# Headlightsv2.net
KiCad netlist of a schematic drawn in EAGLE
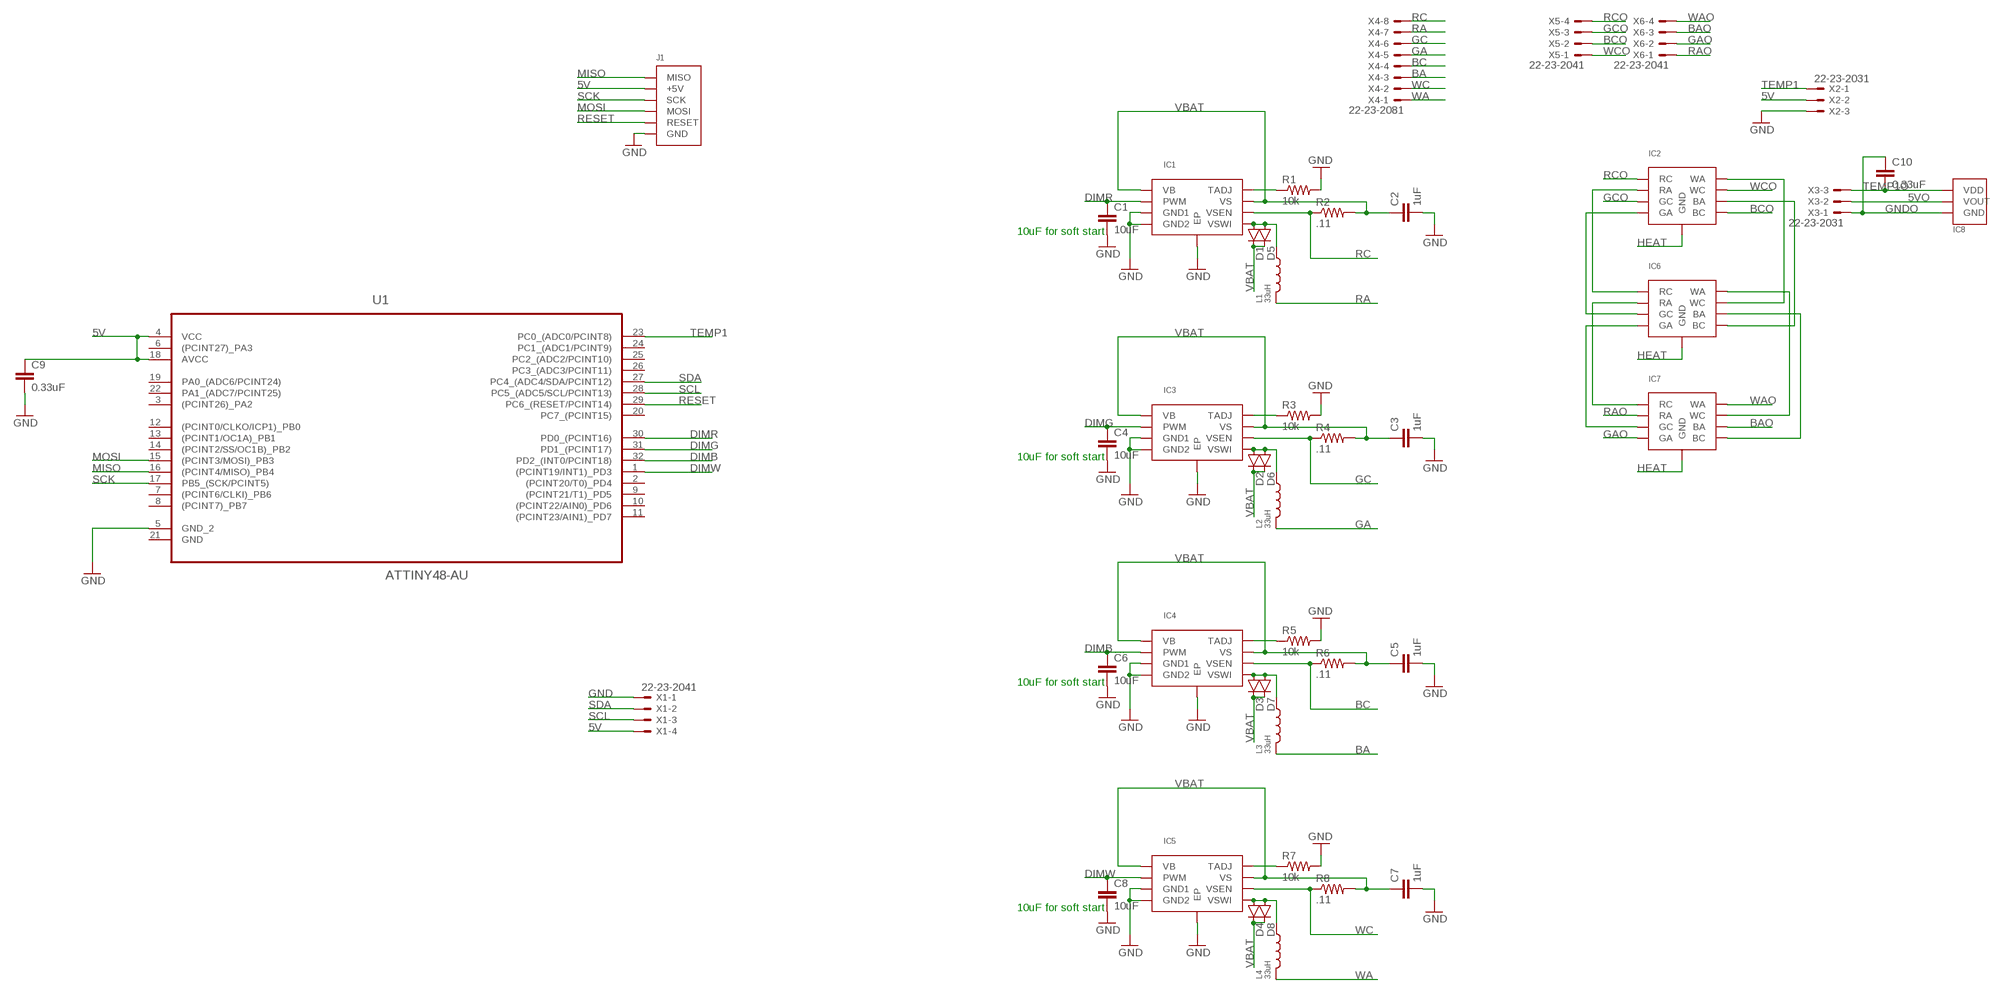
[diagram p0: schematic, sheet 1]

(export (version "E")
  (design (tool "Eeschema 10.0.6"))
  (components
    (comp (ref "C1")
      (value "10uF")
      (footprint "eagle-import:0805-CAP")
      (libsource (lib "eagle-import") (part "10UF10V10%(0805)"))
    )
    (comp (ref "C2")
      (value "1uF")
      (footprint "eagle-import:1206-CAP")
      (libsource (lib "eagle-import") (part "2.2UF50V10%(1206)"))
    )
    (comp (ref "C3")
      (value "1uF")
      (footprint "eagle-import:1206-CAP")
      (libsource (lib "eagle-import") (part "2.2UF50V10%(1206)"))
    )
    (comp (ref "C4")
      (value "10uF")
      (footprint "eagle-import:0805-CAP")
      (libsource (lib "eagle-import") (part "10UF10V10%(0805)"))
    )
    (comp (ref "C5")
      (value "1uF")
      (footprint "eagle-import:1206-CAP")
      (libsource (lib "eagle-import") (part "2.2UF50V10%(1206)"))
    )
    (comp (ref "C6")
      (value "10uF")
      (footprint "eagle-import:0805-CAP")
      (libsource (lib "eagle-import") (part "10UF10V10%(0805)"))
    )
    (comp (ref "C7")
      (value "1uF")
      (footprint "eagle-import:1206-CAP")
      (libsource (lib "eagle-import") (part "2.2UF50V10%(1206)"))
    )
    (comp (ref "C8")
      (value "10uF")
      (footprint "eagle-import:0805-CAP")
      (libsource (lib "eagle-import") (part "10UF10V10%(0805)"))
    )
    (comp (ref "C9")
      (value "0.33uF")
      (footprint "eagle-import:0805-CAP")
      (libsource (lib "eagle-import") (part "0.33UF-50V-10%(0805)"))
    )
    (comp (ref "C10")
      (value "0.33uF")
      (footprint "eagle-import:0805-CAP")
      (libsource (lib "eagle-import") (part "0.33UF-50V-10%(0805)"))
    )
    (comp (ref "D1")
      (value "DIODESMA-ALT")
      (footprint "eagle-import:SMA-DIODE_ALT")
      (libsource (lib "eagle-import") (part "DIODESMA-ALT"))
    )
    (comp (ref "D2")
      (value "DIODESMA-ALT")
      (footprint "eagle-import:SMA-DIODE_ALT")
      (libsource (lib "eagle-import") (part "DIODESMA-ALT"))
    )
    (comp (ref "D3")
      (value "DIODESMA-ALT")
      (footprint "eagle-import:SMA-DIODE_ALT")
      (libsource (lib "eagle-import") (part "DIODESMA-ALT"))
    )
    (comp (ref "D4")
      (value "DIODESMA-ALT")
      (footprint "eagle-import:SMA-DIODE_ALT")
      (libsource (lib "eagle-import") (part "DIODESMA-ALT"))
    )
    (comp (ref "D5")
      (value "DIODESMA-ALT")
      (footprint "eagle-import:SMA-DIODE_ALT")
      (libsource (lib "eagle-import") (part "DIODESMA-ALT"))
    )
    (comp (ref "D6")
      (value "DIODESMA-ALT")
      (footprint "eagle-import:SMA-DIODE_ALT")
      (libsource (lib "eagle-import") (part "DIODESMA-ALT"))
    )
    (comp (ref "D7")
      (value "DIODESMA-ALT")
      (footprint "eagle-import:SMA-DIODE_ALT")
      (libsource (lib "eagle-import") (part "DIODESMA-ALT"))
    )
    (comp (ref "D8")
      (value "DIODESMA-ALT")
      (footprint "eagle-import:SMA-DIODE_ALT")
      (libsource (lib "eagle-import") (part "DIODESMA-ALT"))
    )
    (comp (ref "IC1")
      (value "ILD6150_LED_DRIVER")
      (footprint "eagle-import:PG-DSO-8-27")
      (libsource (lib "eagle-import") (part "ILD6150_LED_DRIVER"))
    )
    (comp (ref "IC2")
      (value "LED_RGBW_CONF2")
      (footprint "eagle-import:LED_RGBW_CUSTOM")
      (libsource (lib "eagle-import") (part "LED_RGBW_CONF2"))
    )
    (comp (ref "IC3")
      (value "ILD6150_LED_DRIVER")
      (footprint "eagle-import:PG-DSO-8-27")
      (libsource (lib "eagle-import") (part "ILD6150_LED_DRIVER"))
    )
    (comp (ref "IC4")
      (value "ILD6150_LED_DRIVER")
      (footprint "eagle-import:PG-DSO-8-27")
      (libsource (lib "eagle-import") (part "ILD6150_LED_DRIVER"))
    )
    (comp (ref "IC5")
      (value "ILD6150_LED_DRIVER")
      (footprint "eagle-import:PG-DSO-8-27")
      (libsource (lib "eagle-import") (part "ILD6150_LED_DRIVER"))
    )
    (comp (ref "IC6")
      (value "LED_RGBW_CONF2")
      (footprint "eagle-import:LED_RGBW_CUSTOM")
      (libsource (lib "eagle-import") (part "LED_RGBW_CONF2"))
    )
    (comp (ref "IC7")
      (value "LED_RGBW_CONF2")
      (footprint "eagle-import:LED_RGBW_CUSTOM")
      (libsource (lib "eagle-import") (part "LED_RGBW_CONF2"))
    )
    (comp (ref "IC8")
      (value "TEMP_MCP9701")
      (footprint "eagle-import:SOT-23-3")
      (libsource (lib "eagle-import") (part "TEMP_MCP9701"))
    )
    (comp (ref "J1")
      (value "ISPHEADER")
      (footprint "eagle-import:2X3PIN_.1'")
      (libsource (lib "eagle-import") (part "ISPHEADER"))
    )
    (comp (ref "L1")
      (value "33uH")
      (footprint "eagle-import:IND_RLB_SERIES")
      (libsource (lib "eagle-import") (part "CHIP_IND4"))
    )
    (comp (ref "L2")
      (value "33uH")
      (footprint "eagle-import:IND_RLB_SERIES")
      (libsource (lib "eagle-import") (part "CHIP_IND4"))
    )
    (comp (ref "L3")
      (value "33uH")
      (footprint "eagle-import:IND_RLB_SERIES")
      (libsource (lib "eagle-import") (part "CHIP_IND4"))
    )
    (comp (ref "L4")
      (value "33uH")
      (footprint "eagle-import:IND_RLB_SERIES")
      (libsource (lib "eagle-import") (part "CHIP_IND4"))
    )
    (comp (ref "R1")
      (value "10k")
      (footprint "eagle-import:0805")
      (libsource (lib "eagle-import") (part "0.3OHM-1/8W-1%(0805)"))
    )
    (comp (ref "R2")
      (value ".11")
      (footprint "eagle-import:R2010")
      (libsource (lib "eagle-import") (part "0.11OHM1/2W1%(2010)"))
    )
    (comp (ref "R3")
      (value "10k")
      (footprint "eagle-import:0805")
      (libsource (lib "eagle-import") (part "0.3OHM-1/8W-1%(0805)"))
    )
    (comp (ref "R4")
      (value ".11")
      (footprint "eagle-import:R2010")
      (libsource (lib "eagle-import") (part "0.11OHM1/2W1%(2010)"))
    )
    (comp (ref "R5")
      (value "10k")
      (footprint "eagle-import:0805")
      (libsource (lib "eagle-import") (part "0.3OHM-1/8W-1%(0805)"))
    )
    (comp (ref "R6")
      (value ".11")
      (footprint "eagle-import:R2010")
      (libsource (lib "eagle-import") (part "0.11OHM1/2W1%(2010)"))
    )
    (comp (ref "R7")
      (value "10k")
      (footprint "eagle-import:0805")
      (libsource (lib "eagle-import") (part "0.3OHM-1/8W-1%(0805)"))
    )
    (comp (ref "R8")
      (value ".11")
      (footprint "eagle-import:R2010")
      (libsource (lib "eagle-import") (part "0.11OHM1/2W1%(2010)"))
    )
    (comp (ref "U1")
      (value "ATTINY48-AU")
      (footprint "eagle-import:QFP80P900X900X120-32N")
      (libsource (lib "eagle-import") (part "ATTINY48-AU"))
    )
    (comp (ref "X1")
      (value "22-23-2041")
      (footprint "eagle-import:22-23-2041")
      (fields (field (name "MF") "MOLEX"))
      (libsource (lib "eagle-import") (part "22-23-2041"))
    )
    (comp (ref "X2")
      (value "22-23-2031")
      (footprint "eagle-import:22-23-2031")
      (fields (field (name "MF") "MOLEX"))
      (libsource (lib "eagle-import") (part "22-23-2031"))
    )
    (comp (ref "X3")
      (value "22-23-2031")
      (footprint "eagle-import:22-23-2031")
      (fields (field (name "MF") "MOLEX"))
      (libsource (lib "eagle-import") (part "22-23-2031"))
    )
    (comp (ref "X4")
      (value "22-23-2081")
      (footprint "eagle-import:22-23-2081")
      (fields (field (name "MF") "MOLEX"))
      (libsource (lib "eagle-import") (part "22-23-2081"))
    )
    (comp (ref "X5")
      (value "22-23-2041")
      (footprint "eagle-import:22-23-2041")
      (fields (field (name "MF") "MOLEX"))
      (libsource (lib "eagle-import") (part "22-23-2041"))
    )
    (comp (ref "X6")
      (value "22-23-2041")
      (footprint "eagle-import:22-23-2041")
      (fields (field (name "MF") "MOLEX"))
      (libsource (lib "eagle-import") (part "22-23-2041"))
    )
  )
  (nets
    (net (code "1") (name "/5V") (class "Default")
      (node (ref "C9") (pin "1") (pinfunction "1_1") (pintype "passive"))
      (node (ref "J1") (pin "P$2") (pinfunction "+5V_P$2") (pintype "bidirectional"))
      (node (ref "U1") (pin "18") (pinfunction "AVCC_18") (pintype "power_in"))
      (node (ref "U1") (pin "4") (pinfunction "VCC_4") (pintype "power_in"))
      (node (ref "X1") (pin "4") (pinfunction "S_4") (pintype "passive"))
      (node (ref "X2") (pin "2") (pinfunction "S_2") (pintype "passive"))
    )
    (net (code "2") (name "/5VO") (class "Default")
      (node (ref "IC8") (pin "2") (pinfunction "VOUT_2") (pintype "bidirectional"))
      (node (ref "X3") (pin "2") (pinfunction "S_2") (pintype "passive"))
    )
    (net (code "3") (name "/BA") (class "Default")
      (node (ref "L3") (pin "P$1") (pinfunction "P$1_P$1") (pintype "bidirectional"))
      (node (ref "X4") (pin "3") (pinfunction "S_3") (pintype "passive"))
    )
    (net (code "4") (name "/BAO") (class "Default")
      (node (ref "IC7") (pin "6") (pinfunction "BA_6") (pintype "bidirectional"))
      (node (ref "X6") (pin "3") (pinfunction "S_3") (pintype "passive"))
    )
    (net (code "5") (name "/BC") (class "Default")
      (node (ref "IC4") (pin "P$6") (pinfunction "VSEN_P$6") (pintype "bidirectional"))
      (node (ref "R6") (pin "1") (pinfunction "1_1") (pintype "passive"))
      (node (ref "X4") (pin "4") (pinfunction "S_4") (pintype "passive"))
    )
    (net (code "6") (name "/BCO") (class "Default")
      (node (ref "IC2") (pin "5") (pinfunction "BC_5") (pintype "bidirectional"))
      (node (ref "X5") (pin "2") (pinfunction "S_2") (pintype "passive"))
    )
    (net (code "7") (name "/DIMB") (class "Default")
      (node (ref "C6") (pin "1") (pinfunction "1_1") (pintype "passive"))
      (node (ref "IC4") (pin "P$2") (pinfunction "PWM_P$2") (pintype "bidirectional"))
      (node (ref "U1") (pin "32") (pinfunction "PD2_(INT0/PCINT18)_32") (pintype "bidirectional"))
    )
    (net (code "8") (name "/DIMG") (class "Default")
      (node (ref "C4") (pin "1") (pinfunction "1_1") (pintype "passive"))
      (node (ref "IC3") (pin "P$2") (pinfunction "PWM_P$2") (pintype "bidirectional"))
      (node (ref "U1") (pin "31") (pinfunction "PD1_(PCINT17)_31") (pintype "bidirectional"))
    )
    (net (code "9") (name "/DIMR") (class "Default")
      (node (ref "C1") (pin "1") (pinfunction "1_1") (pintype "passive"))
      (node (ref "IC1") (pin "P$2") (pinfunction "PWM_P$2") (pintype "bidirectional"))
      (node (ref "U1") (pin "30") (pinfunction "PD0_(PCINT16)_30") (pintype "bidirectional"))
    )
    (net (code "10") (name "/DIMW") (class "Default")
      (node (ref "C8") (pin "1") (pinfunction "1_1") (pintype "passive"))
      (node (ref "IC5") (pin "P$2") (pinfunction "PWM_P$2") (pintype "bidirectional"))
      (node (ref "U1") (pin "1") (pinfunction "(PCINT19/INT1)_PD3_1") (pintype "bidirectional"))
    )
    (net (code "11") (name "/GA") (class "Default")
      (node (ref "L2") (pin "P$1") (pinfunction "P$1_P$1") (pintype "bidirectional"))
      (node (ref "X4") (pin "5") (pinfunction "S_5") (pintype "passive"))
    )
    (net (code "12") (name "/GAO") (class "Default")
      (node (ref "IC7") (pin "4") (pinfunction "GA_4") (pintype "bidirectional"))
      (node (ref "X6") (pin "2") (pinfunction "S_2") (pintype "passive"))
    )
    (net (code "13") (name "/GC") (class "Default")
      (node (ref "IC3") (pin "P$6") (pinfunction "VSEN_P$6") (pintype "bidirectional"))
      (node (ref "R4") (pin "1") (pinfunction "1_1") (pintype "passive"))
      (node (ref "X4") (pin "6") (pinfunction "S_6") (pintype "passive"))
    )
    (net (code "14") (name "/GCO") (class "Default")
      (node (ref "IC2") (pin "3") (pinfunction "GC_3") (pintype "bidirectional"))
      (node (ref "X5") (pin "3") (pinfunction "S_3") (pintype "passive"))
    )
    (net (code "15") (name "/GNDO") (class "Default")
      (node (ref "C10") (pin "1") (pinfunction "1_1") (pintype "passive"))
      (node (ref "IC8") (pin "3") (pinfunction "GND_3") (pintype "bidirectional"))
      (node (ref "X3") (pin "1") (pinfunction "S_1") (pintype "passive"))
    )
    (net (code "16") (name "/HEAT") (class "Default")
      (node (ref "IC2") (pin "9") (pinfunction "GND_9") (pintype "bidirectional"))
      (node (ref "IC6") (pin "9") (pinfunction "GND_9") (pintype "bidirectional"))
      (node (ref "IC7") (pin "9") (pinfunction "GND_9") (pintype "bidirectional"))
    )
    (net (code "17") (name "/MISO") (class "Default")
      (node (ref "J1") (pin "P$1") (pinfunction "MISO_P$1") (pintype "bidirectional"))
      (node (ref "U1") (pin "16") (pinfunction "(PCINT4/MISO)_PB4_16") (pintype "bidirectional"))
    )
    (net (code "18") (name "/MOSI") (class "Default")
      (node (ref "J1") (pin "P$4") (pinfunction "MOSI_P$4") (pintype "bidirectional"))
      (node (ref "U1") (pin "15") (pinfunction "(PCINT3/MOSI)_PB3_15") (pintype "bidirectional"))
    )
    (net (code "19") (name "/RA") (class "Default")
      (node (ref "L1") (pin "P$1") (pinfunction "P$1_P$1") (pintype "bidirectional"))
      (node (ref "X4") (pin "7") (pinfunction "S_7") (pintype "passive"))
    )
    (net (code "20") (name "/RAO") (class "Default")
      (node (ref "IC7") (pin "2") (pinfunction "RA_2") (pintype "bidirectional"))
      (node (ref "X6") (pin "1") (pinfunction "S_1") (pintype "passive"))
    )
    (net (code "21") (name "/RC") (class "Default")
      (node (ref "IC1") (pin "P$6") (pinfunction "VSEN_P$6") (pintype "bidirectional"))
      (node (ref "R2") (pin "1") (pinfunction "1_1") (pintype "passive"))
      (node (ref "X4") (pin "8") (pinfunction "S_8") (pintype "passive"))
    )
    (net (code "22") (name "/RCO") (class "Default")
      (node (ref "IC2") (pin "1") (pinfunction "RC_1") (pintype "bidirectional"))
      (node (ref "X5") (pin "4") (pinfunction "S_4") (pintype "passive"))
    )
    (net (code "23") (name "/RESET") (class "Default")
      (node (ref "J1") (pin "P$5") (pinfunction "RESET_P$5") (pintype "bidirectional"))
      (node (ref "U1") (pin "29") (pinfunction "PC6_(RESET/PCINT14)_29") (pintype "bidirectional"))
    )
    (net (code "24") (name "/SCK") (class "Default")
      (node (ref "J1") (pin "P$3") (pinfunction "SCK_P$3") (pintype "bidirectional"))
      (node (ref "U1") (pin "17") (pinfunction "PB5_(SCK/PCINT5)_17") (pintype "bidirectional"))
    )
    (net (code "25") (name "/SCL") (class "Default")
      (node (ref "U1") (pin "28") (pinfunction "PC5_(ADC5/SCL/PCINT13)_28") (pintype "bidirectional"))
      (node (ref "X1") (pin "3") (pinfunction "S_3") (pintype "passive"))
    )
    (net (code "26") (name "/SDA") (class "Default")
      (node (ref "U1") (pin "27") (pinfunction "PC4_(ADC4/SDA/PCINT12)_27") (pintype "bidirectional"))
      (node (ref "X1") (pin "2") (pinfunction "S_2") (pintype "passive"))
    )
    (net (code "27") (name "/TEMP1") (class "Default")
      (node (ref "U1") (pin "23") (pinfunction "PC0_(ADC0/PCINT8)_23") (pintype "bidirectional"))
      (node (ref "X2") (pin "1") (pinfunction "S_1") (pintype "passive"))
    )
    (net (code "28") (name "/TEMP1O") (class "Default")
      (node (ref "C10") (pin "2") (pinfunction "2_2") (pintype "passive"))
      (node (ref "IC8") (pin "1") (pinfunction "VDD_1") (pintype "bidirectional"))
      (node (ref "X3") (pin "3") (pinfunction "S_3") (pintype "passive"))
    )
    (net (code "29") (name "/VBAT") (class "Default")
      (node (ref "C2") (pin "1") (pinfunction "1_1") (pintype "passive"))
      (node (ref "C3") (pin "1") (pinfunction "1_1") (pintype "passive"))
      (node (ref "C5") (pin "1") (pinfunction "1_1") (pintype "passive"))
      (node (ref "C7") (pin "1") (pinfunction "1_1") (pintype "passive"))
      (node (ref "D1") (pin "C") (pinfunction "C_C") (pintype "passive"))
      (node (ref "D2") (pin "C") (pinfunction "C_C") (pintype "passive"))
      (node (ref "D3") (pin "C") (pinfunction "C_C") (pintype "passive"))
      (node (ref "D4") (pin "C") (pinfunction "C_C") (pintype "passive"))
      (node (ref "D5") (pin "C") (pinfunction "C_C") (pintype "passive"))
      (node (ref "D6") (pin "C") (pinfunction "C_C") (pintype "passive"))
      (node (ref "D7") (pin "C") (pinfunction "C_C") (pintype "passive"))
      (node (ref "D8") (pin "C") (pinfunction "C_C") (pintype "passive"))
      (node (ref "IC1") (pin "P$1") (pinfunction "VB_P$1") (pintype "bidirectional"))
      (node (ref "IC1") (pin "P$7") (pinfunction "VS_P$7") (pintype "bidirectional"))
      (node (ref "IC3") (pin "P$1") (pinfunction "VB_P$1") (pintype "bidirectional"))
      (node (ref "IC3") (pin "P$7") (pinfunction "VS_P$7") (pintype "bidirectional"))
      (node (ref "IC4") (pin "P$1") (pinfunction "VB_P$1") (pintype "bidirectional"))
      (node (ref "IC4") (pin "P$7") (pinfunction "VS_P$7") (pintype "bidirectional"))
      (node (ref "IC5") (pin "P$1") (pinfunction "VB_P$1") (pintype "bidirectional"))
      (node (ref "IC5") (pin "P$7") (pinfunction "VS_P$7") (pintype "bidirectional"))
      (node (ref "R2") (pin "2") (pinfunction "2_2") (pintype "passive"))
      (node (ref "R4") (pin "2") (pinfunction "2_2") (pintype "passive"))
      (node (ref "R6") (pin "2") (pinfunction "2_2") (pintype "passive"))
      (node (ref "R8") (pin "2") (pinfunction "2_2") (pintype "passive"))
    )
    (net (code "30") (name "/WA") (class "Default")
      (node (ref "L4") (pin "P$1") (pinfunction "P$1_P$1") (pintype "bidirectional"))
      (node (ref "X4") (pin "1") (pinfunction "S_1") (pintype "passive"))
    )
    (net (code "31") (name "/WAO") (class "Default")
      (node (ref "IC7") (pin "8") (pinfunction "WA_8") (pintype "bidirectional"))
      (node (ref "X6") (pin "4") (pinfunction "S_4") (pintype "passive"))
    )
    (net (code "32") (name "/WC") (class "Default")
      (node (ref "IC5") (pin "P$6") (pinfunction "VSEN_P$6") (pintype "bidirectional"))
      (node (ref "R8") (pin "1") (pinfunction "1_1") (pintype "passive"))
      (node (ref "X4") (pin "2") (pinfunction "S_2") (pintype "passive"))
    )
    (net (code "33") (name "/WCO") (class "Default")
      (node (ref "IC2") (pin "7") (pinfunction "WC_7") (pintype "bidirectional"))
      (node (ref "X5") (pin "1") (pinfunction "S_1") (pintype "passive"))
    )
    (net (code "34") (name "GND") (class "Default")
      (node (ref "C1") (pin "2") (pinfunction "2_2") (pintype "passive"))
      (node (ref "C2") (pin "2") (pinfunction "2_2") (pintype "passive"))
      (node (ref "C3") (pin "2") (pinfunction "2_2") (pintype "passive"))
      (node (ref "C4") (pin "2") (pinfunction "2_2") (pintype "passive"))
      (node (ref "C5") (pin "2") (pinfunction "2_2") (pintype "passive"))
      (node (ref "C6") (pin "2") (pinfunction "2_2") (pintype "passive"))
      (node (ref "C7") (pin "2") (pinfunction "2_2") (pintype "passive"))
      (node (ref "C8") (pin "2") (pinfunction "2_2") (pintype "passive"))
      (node (ref "C9") (pin "2") (pinfunction "2_2") (pintype "passive"))
      (node (ref "IC1") (pin "P$3") (pinfunction "GND1_P$3") (pintype "bidirectional"))
      (node (ref "IC1") (pin "P$4") (pinfunction "GND2_P$4") (pintype "bidirectional"))
      (node (ref "IC1") (pin "P$9") (pinfunction "EP_P$9") (pintype "bidirectional"))
      (node (ref "IC3") (pin "P$3") (pinfunction "GND1_P$3") (pintype "bidirectional"))
      (node (ref "IC3") (pin "P$4") (pinfunction "GND2_P$4") (pintype "bidirectional"))
      (node (ref "IC3") (pin "P$9") (pinfunction "EP_P$9") (pintype "bidirectional"))
      (node (ref "IC4") (pin "P$3") (pinfunction "GND1_P$3") (pintype "bidirectional"))
      (node (ref "IC4") (pin "P$4") (pinfunction "GND2_P$4") (pintype "bidirectional"))
      (node (ref "IC4") (pin "P$9") (pinfunction "EP_P$9") (pintype "bidirectional"))
      (node (ref "IC5") (pin "P$3") (pinfunction "GND1_P$3") (pintype "bidirectional"))
      (node (ref "IC5") (pin "P$4") (pinfunction "GND2_P$4") (pintype "bidirectional"))
      (node (ref "IC5") (pin "P$9") (pinfunction "EP_P$9") (pintype "bidirectional"))
      (node (ref "J1") (pin "P$6") (pinfunction "GND_P$6") (pintype "bidirectional"))
      (node (ref "R1") (pin "2") (pinfunction "2_2") (pintype "passive"))
      (node (ref "R3") (pin "2") (pinfunction "2_2") (pintype "passive"))
      (node (ref "R5") (pin "2") (pinfunction "2_2") (pintype "passive"))
      (node (ref "R7") (pin "2") (pinfunction "2_2") (pintype "passive"))
      (node (ref "U1") (pin "5") (pinfunction "GND_2_5") (pintype "passive"))
      (node (ref "X1") (pin "1") (pinfunction "S_1") (pintype "passive"))
      (node (ref "X2") (pin "3") (pinfunction "S_3") (pintype "passive"))
    )
    (net (code "35") (name "Net-(IC1-TADJ)") (class "Default")
      (node (ref "IC1") (pin "P$8") (pinfunction "TADJ_P$8") (pintype "bidirectional"))
      (node (ref "R1") (pin "1") (pinfunction "1_1") (pintype "passive"))
    )
    (net (code "36") (name "Net-(IC1-VSWI)") (class "Default")
      (node (ref "D1") (pin "A") (pinfunction "A_A") (pintype "passive"))
      (node (ref "D5") (pin "A") (pinfunction "A_A") (pintype "passive"))
      (node (ref "IC1") (pin "P$5") (pinfunction "VSWI_P$5") (pintype "bidirectional"))
      (node (ref "L1") (pin "P$2") (pinfunction "P$2_P$2") (pintype "bidirectional"))
    )
    (net (code "37") (name "Net-(IC2-BA)") (class "Default")
      (node (ref "IC2") (pin "6") (pinfunction "BA_6") (pintype "bidirectional"))
      (node (ref "IC6") (pin "5") (pinfunction "BC_5") (pintype "bidirectional"))
    )
    (net (code "38") (name "Net-(IC2-GA)") (class "Default")
      (node (ref "IC2") (pin "4") (pinfunction "GA_4") (pintype "bidirectional"))
      (node (ref "IC6") (pin "3") (pinfunction "GC_3") (pintype "bidirectional"))
    )
    (net (code "39") (name "Net-(IC2-RA)") (class "Default")
      (node (ref "IC2") (pin "2") (pinfunction "RA_2") (pintype "bidirectional"))
      (node (ref "IC6") (pin "1") (pinfunction "RC_1") (pintype "bidirectional"))
    )
    (net (code "40") (name "Net-(IC2-WA)") (class "Default")
      (node (ref "IC2") (pin "8") (pinfunction "WA_8") (pintype "bidirectional"))
      (node (ref "IC6") (pin "7") (pinfunction "WC_7") (pintype "bidirectional"))
    )
    (net (code "41") (name "Net-(IC3-TADJ)") (class "Default")
      (node (ref "IC3") (pin "P$8") (pinfunction "TADJ_P$8") (pintype "bidirectional"))
      (node (ref "R3") (pin "1") (pinfunction "1_1") (pintype "passive"))
    )
    (net (code "42") (name "Net-(IC3-VSWI)") (class "Default")
      (node (ref "D2") (pin "A") (pinfunction "A_A") (pintype "passive"))
      (node (ref "D6") (pin "A") (pinfunction "A_A") (pintype "passive"))
      (node (ref "IC3") (pin "P$5") (pinfunction "VSWI_P$5") (pintype "bidirectional"))
      (node (ref "L2") (pin "P$2") (pinfunction "P$2_P$2") (pintype "bidirectional"))
    )
    (net (code "43") (name "Net-(IC4-TADJ)") (class "Default")
      (node (ref "IC4") (pin "P$8") (pinfunction "TADJ_P$8") (pintype "bidirectional"))
      (node (ref "R5") (pin "1") (pinfunction "1_1") (pintype "passive"))
    )
    (net (code "44") (name "Net-(IC4-VSWI)") (class "Default")
      (node (ref "D3") (pin "A") (pinfunction "A_A") (pintype "passive"))
      (node (ref "D7") (pin "A") (pinfunction "A_A") (pintype "passive"))
      (node (ref "IC4") (pin "P$5") (pinfunction "VSWI_P$5") (pintype "bidirectional"))
      (node (ref "L3") (pin "P$2") (pinfunction "P$2_P$2") (pintype "bidirectional"))
    )
    (net (code "45") (name "Net-(IC5-TADJ)") (class "Default")
      (node (ref "IC5") (pin "P$8") (pinfunction "TADJ_P$8") (pintype "bidirectional"))
      (node (ref "R7") (pin "1") (pinfunction "1_1") (pintype "passive"))
    )
    (net (code "46") (name "Net-(IC5-VSWI)") (class "Default")
      (node (ref "D4") (pin "A") (pinfunction "A_A") (pintype "passive"))
      (node (ref "D8") (pin "A") (pinfunction "A_A") (pintype "passive"))
      (node (ref "IC5") (pin "P$5") (pinfunction "VSWI_P$5") (pintype "bidirectional"))
      (node (ref "L4") (pin "P$2") (pinfunction "P$2_P$2") (pintype "bidirectional"))
    )
    (net (code "47") (name "Net-(IC6-BA)") (class "Default")
      (node (ref "IC6") (pin "6") (pinfunction "BA_6") (pintype "bidirectional"))
      (node (ref "IC7") (pin "5") (pinfunction "BC_5") (pintype "bidirectional"))
    )
    (net (code "48") (name "Net-(IC6-GA)") (class "Default")
      (node (ref "IC6") (pin "4") (pinfunction "GA_4") (pintype "bidirectional"))
      (node (ref "IC7") (pin "3") (pinfunction "GC_3") (pintype "bidirectional"))
    )
    (net (code "49") (name "Net-(IC6-RA)") (class "Default")
      (node (ref "IC6") (pin "2") (pinfunction "RA_2") (pintype "bidirectional"))
      (node (ref "IC7") (pin "1") (pinfunction "RC_1") (pintype "bidirectional"))
    )
    (net (code "50") (name "Net-(IC6-WA)") (class "Default")
      (node (ref "IC6") (pin "8") (pinfunction "WA_8") (pintype "bidirectional"))
      (node (ref "IC7") (pin "7") (pinfunction "WC_7") (pintype "bidirectional"))
    )
    (net (code "51") (name "unconnected-(U1-(PCINT0{slash}CLKO{slash}ICP1)_PB0-Pad12)") (class "Default")
      (node (ref "U1") (pin "12") (pinfunction "(PCINT0/CLKO/ICP1)_PB0_12") (pintype "bidirectional"))
    )
    (net (code "52") (name "unconnected-(U1-(PCINT1{slash}OC1A)_PB1-Pad13)") (class "Default")
      (node (ref "U1") (pin "13") (pinfunction "(PCINT1/OC1A)_PB1_13") (pintype "bidirectional"))
    )
    (net (code "53") (name "unconnected-(U1-(PCINT2{slash}SS{slash}OC1B)_PB2-Pad14)") (class "Default")
      (node (ref "U1") (pin "14") (pinfunction "(PCINT2/SS/OC1B)_PB2_14") (pintype "bidirectional"))
    )
    (net (code "54") (name "unconnected-(U1-(PCINT6{slash}CLKI)_PB6-Pad7)") (class "Default")
      (node (ref "U1") (pin "7") (pinfunction "(PCINT6/CLKI)_PB6_7") (pintype "bidirectional"))
    )
    (net (code "55") (name "unconnected-(U1-(PCINT7)_PB7-Pad8)") (class "Default")
      (node (ref "U1") (pin "8") (pinfunction "(PCINT7)_PB7_8") (pintype "bidirectional"))
    )
    (net (code "56") (name "unconnected-(U1-(PCINT20{slash}T0)_PD4-Pad2)") (class "Default")
      (node (ref "U1") (pin "2") (pinfunction "(PCINT20/T0)_PD4_2") (pintype "bidirectional"))
    )
    (net (code "57") (name "unconnected-(U1-(PCINT21{slash}T1)_PD5-Pad9)") (class "Default")
      (node (ref "U1") (pin "9") (pinfunction "(PCINT21/T1)_PD5_9") (pintype "bidirectional"))
    )
    (net (code "58") (name "unconnected-(U1-(PCINT22{slash}AIN0)_PD6-Pad10)") (class "Default")
      (node (ref "U1") (pin "10") (pinfunction "(PCINT22/AIN0)_PD6_10") (pintype "bidirectional"))
    )
    (net (code "59") (name "unconnected-(U1-(PCINT23{slash}AIN1)_PD7-Pad11)") (class "Default")
      (node (ref "U1") (pin "11") (pinfunction "(PCINT23/AIN1)_PD7_11") (pintype "bidirectional"))
    )
    (net (code "60") (name "unconnected-(U1-(PCINT26)_PA2-Pad3)") (class "Default")
      (node (ref "U1") (pin "3") (pinfunction "(PCINT26)_PA2_3") (pintype "bidirectional"))
    )
    (net (code "61") (name "unconnected-(U1-(PCINT27)_PA3-Pad6)") (class "Default")
      (node (ref "U1") (pin "6") (pinfunction "(PCINT27)_PA3_6") (pintype "bidirectional"))
    )
    (net (code "62") (name "unconnected-(U1-GND-Pad21)") (class "Default")
      (node (ref "U1") (pin "21") (pinfunction "GND_21") (pintype "passive"))
    )
    (net (code "63") (name "unconnected-(U1-PA0_(ADC6{slash}PCINT24)-Pad19)") (class "Default")
      (node (ref "U1") (pin "19") (pinfunction "PA0_(ADC6/PCINT24)_19") (pintype "bidirectional"))
    )
    (net (code "64") (name "unconnected-(U1-PA1_(ADC7{slash}PCINT25)-Pad22)") (class "Default")
      (node (ref "U1") (pin "22") (pinfunction "PA1_(ADC7/PCINT25)_22") (pintype "bidirectional"))
    )
    (net (code "65") (name "unconnected-(U1-PC1_(ADC1{slash}PCINT9)-Pad24)") (class "Default")
      (node (ref "U1") (pin "24") (pinfunction "PC1_(ADC1/PCINT9)_24") (pintype "bidirectional"))
    )
    (net (code "66") (name "unconnected-(U1-PC2_(ADC2{slash}PCINT10)-Pad25)") (class "Default")
      (node (ref "U1") (pin "25") (pinfunction "PC2_(ADC2/PCINT10)_25") (pintype "bidirectional"))
    )
    (net (code "67") (name "unconnected-(U1-PC3_(ADC3{slash}PCINT11)-Pad26)") (class "Default")
      (node (ref "U1") (pin "26") (pinfunction "PC3_(ADC3/PCINT11)_26") (pintype "bidirectional"))
    )
    (net (code "68") (name "unconnected-(U1-PC7_(PCINT15)-Pad20)") (class "Default")
      (node (ref "U1") (pin "20") (pinfunction "PC7_(PCINT15)_20") (pintype "bidirectional"))
    )
  )
)
